# H1FR50.net
KiCad netlist of a schematic drawn in EAGLE
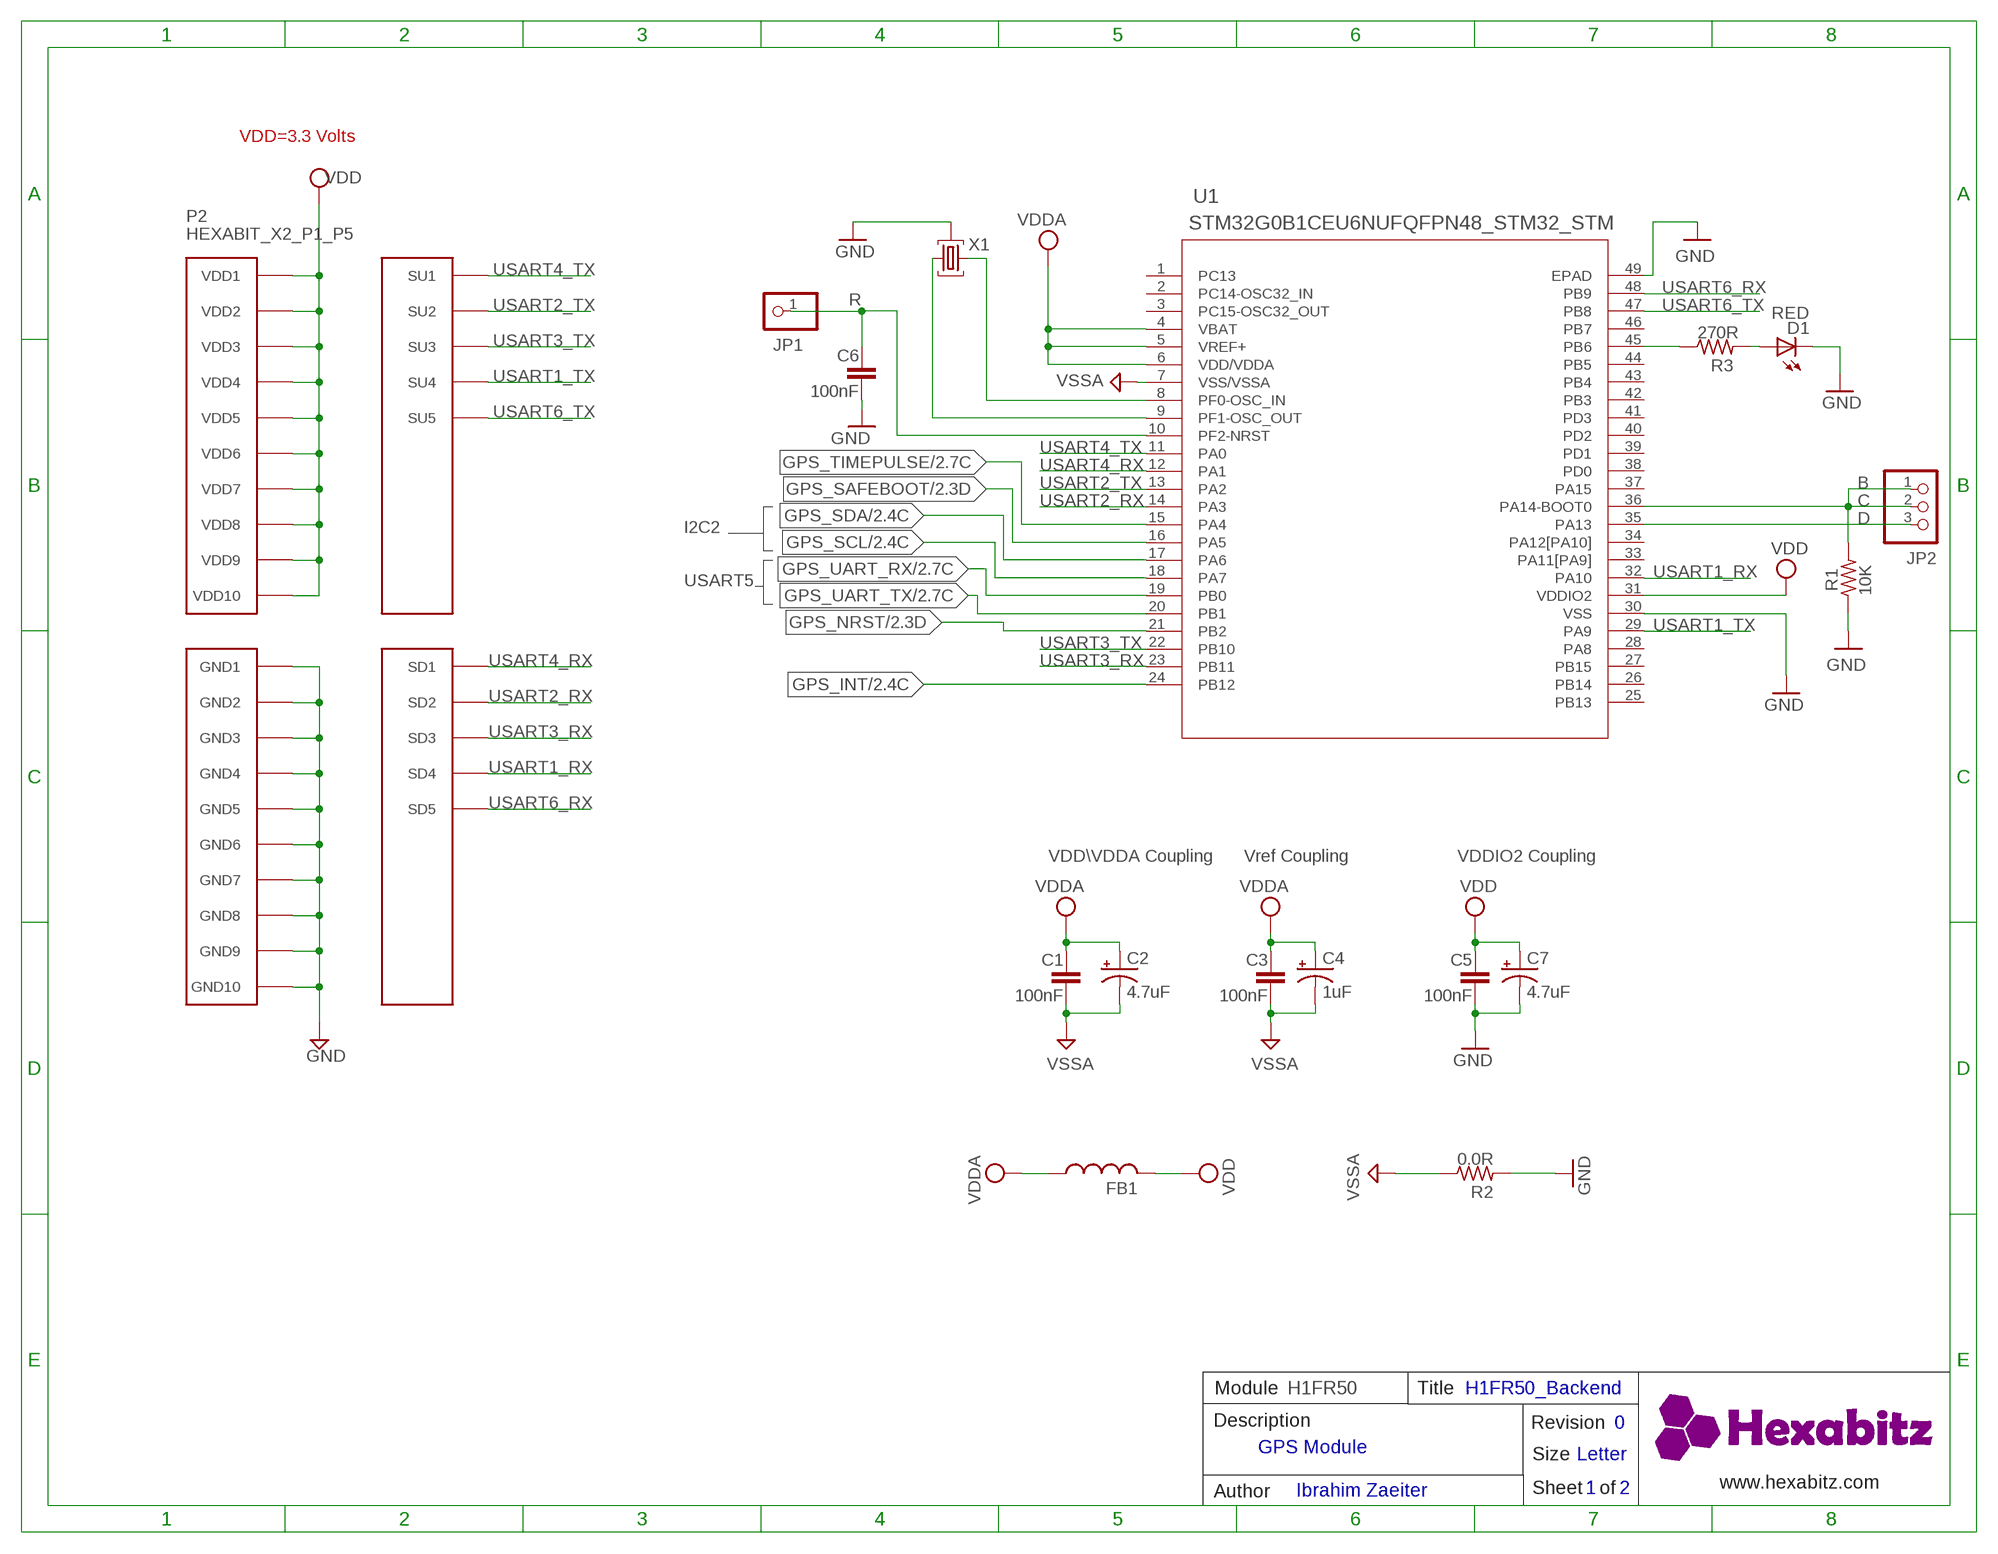
[diagram p0: schematic, sheet 1]
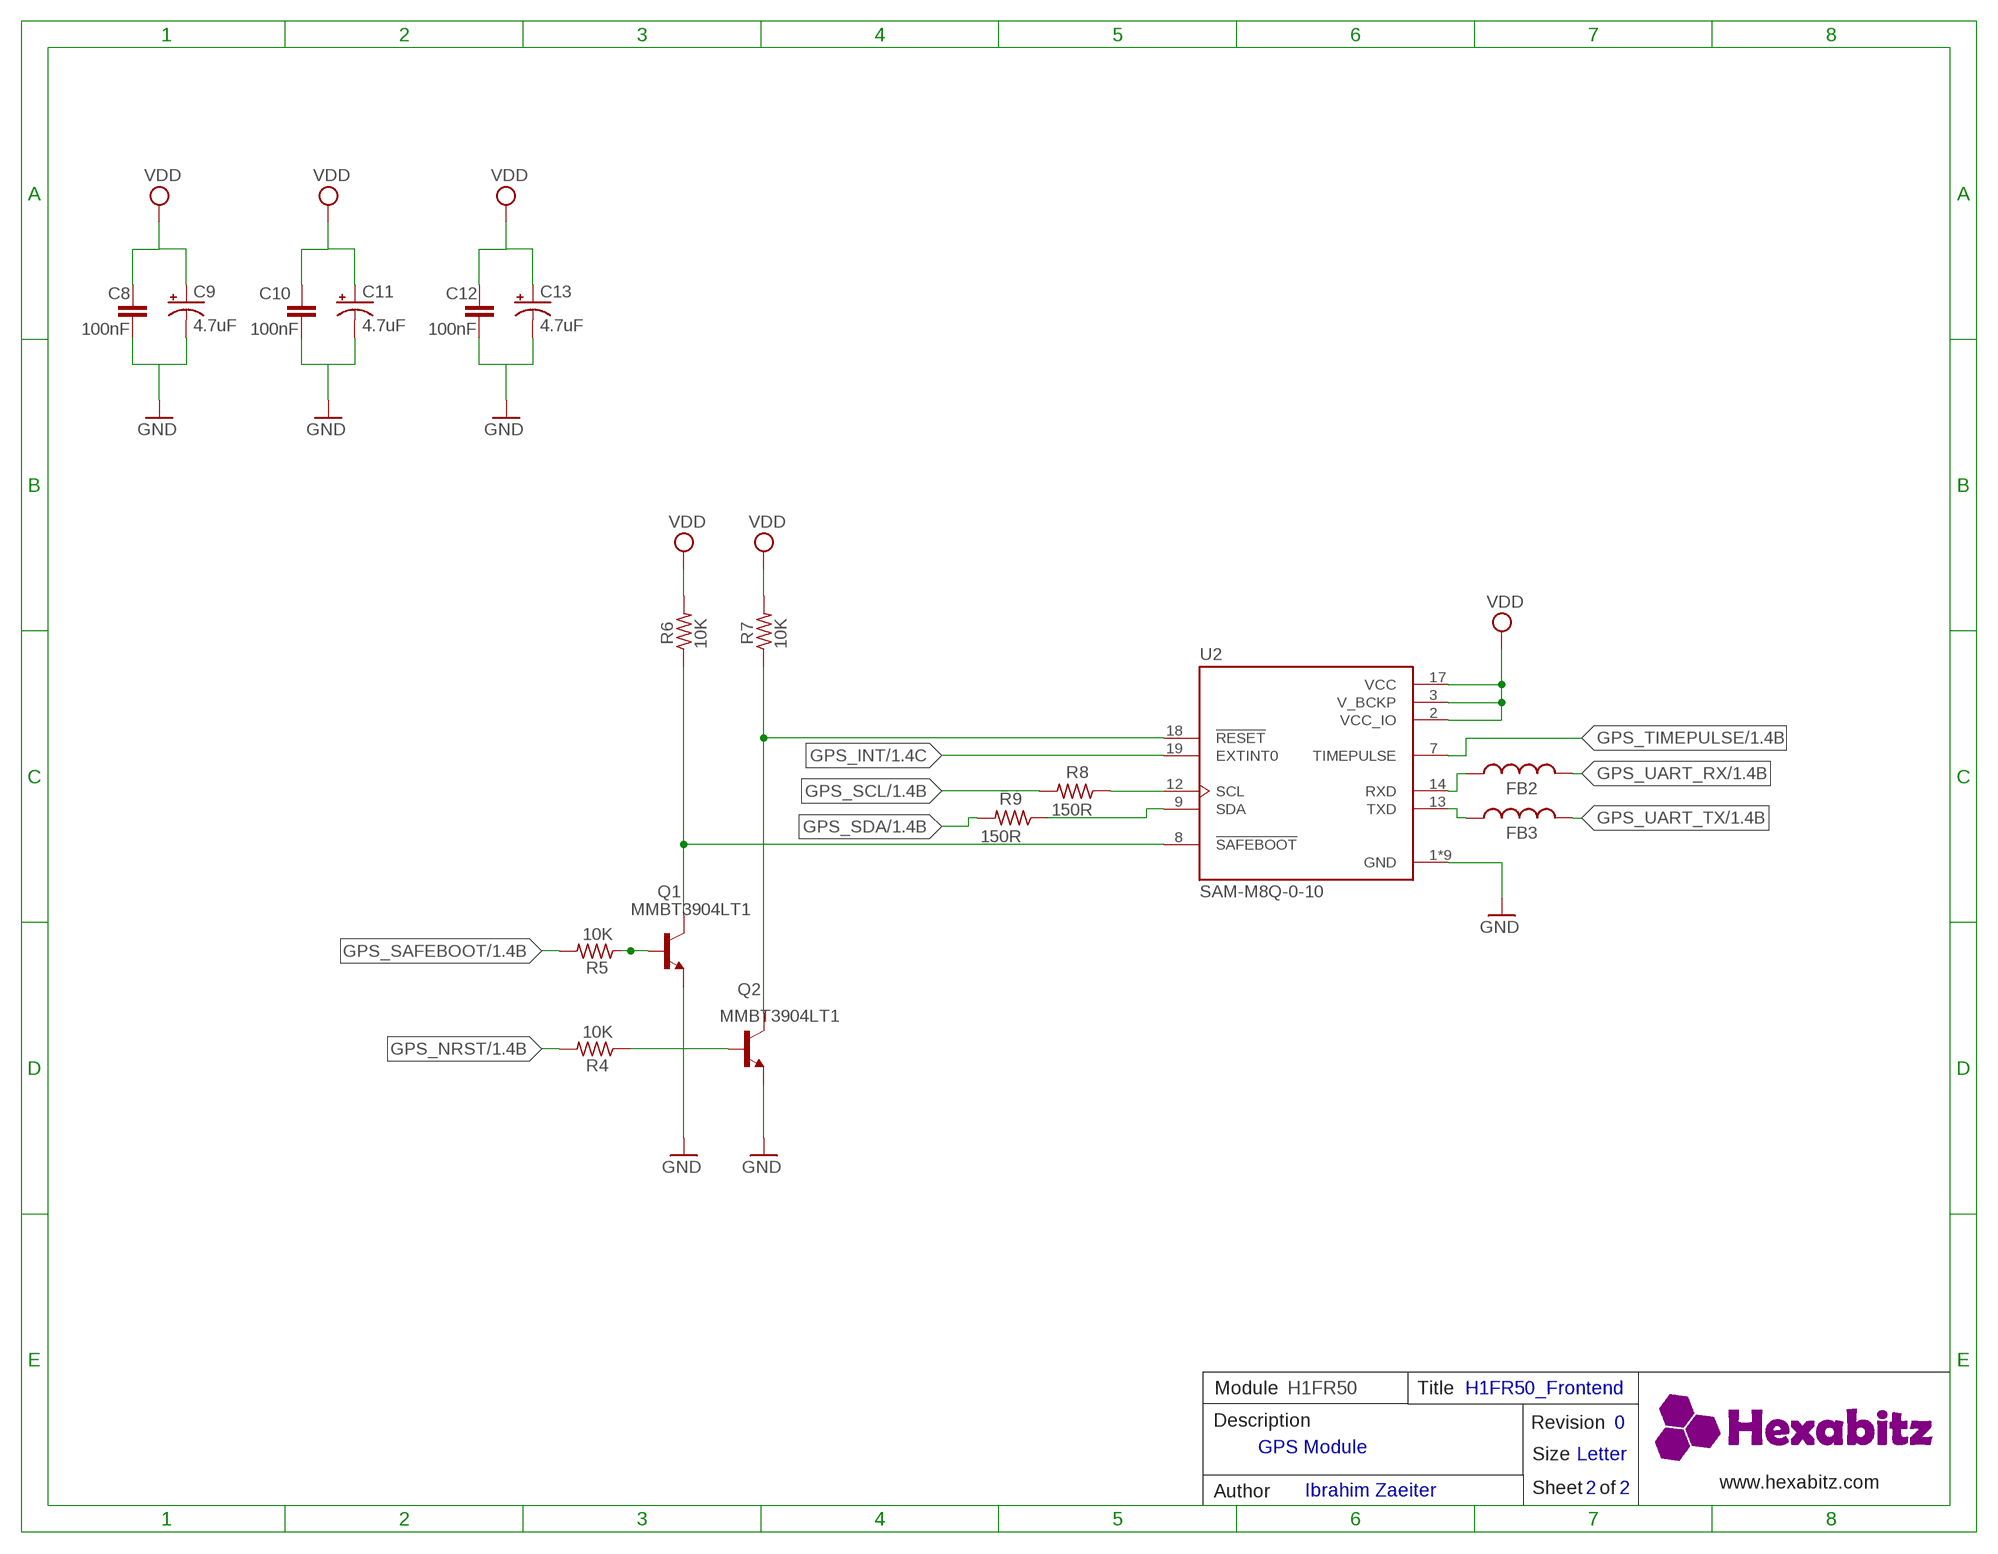
[diagram p1: schematic, sheet 2]

(export (version "E")
  (design (tool "Eeschema 10.0.6"))
  (components
    (comp (ref "C8")
      (value "100nF")
      (footprint "eagle-import:C-0603")
      (libsource (lib "eagle-import") (part "C-0603"))
    )
    (comp (ref "C9")
      (value "4.7uF")
      (footprint "eagle-import:C-0805-POL")
      (libsource (lib "eagle-import") (part "C-0805-POL"))
    )
    (comp (ref "C10")
      (value "100nF")
      (footprint "eagle-import:C-0603")
      (libsource (lib "eagle-import") (part "C-0603"))
    )
    (comp (ref "C11")
      (value "4.7uF")
      (footprint "eagle-import:C-0805-POL")
      (libsource (lib "eagle-import") (part "C-0805-POL"))
    )
    (comp (ref "C12")
      (value "100nF")
      (footprint "eagle-import:C-0603")
      (libsource (lib "eagle-import") (part "C-0603"))
    )
    (comp (ref "C13")
      (value "4.7uF")
      (footprint "eagle-import:C-0805-POL")
      (libsource (lib "eagle-import") (part "C-0805-POL"))
    )
    (comp (ref "FB2")
      (value "BLM18KG601SN1D")
      (footprint "eagle-import:FB-0603")
      (libsource (lib "eagle-import") (part "FB-0603"))
    )
    (comp (ref "FB3")
      (value "BLM18KG601SN1D")
      (footprint "eagle-import:FB-0603")
      (libsource (lib "eagle-import") (part "FB-0603"))
    )
    (comp (ref "Q1")
      (value "MMBT3904LT1")
      (footprint "eagle-import:MMBT3904LT1")
      (libsource (lib "eagle-import") (part "MMBT3904LT1"))
    )
    (comp (ref "Q2")
      (value "MMBT3904LT1")
      (footprint "eagle-import:MMBT3904LT1")
      (libsource (lib "eagle-import") (part "MMBT3904LT1"))
    )
    (comp (ref "R4")
      (value "10K")
      (footprint "eagle-import:R-0603")
      (libsource (lib "eagle-import") (part "R-0603"))
    )
    (comp (ref "R5")
      (value "10K")
      (footprint "eagle-import:R-0603")
      (libsource (lib "eagle-import") (part "R-0603"))
    )
    (comp (ref "R6")
      (value "10K")
      (footprint "eagle-import:R-0603")
      (libsource (lib "eagle-import") (part "R-0603"))
    )
    (comp (ref "R7")
      (value "10K")
      (footprint "eagle-import:R-0603")
      (libsource (lib "eagle-import") (part "R-0603"))
    )
    (comp (ref "R8")
      (value "150R")
      (footprint "eagle-import:R-0603")
      (fields (field (name "MPN") "CRCW0603150RFKEA"))
      (libsource (lib "eagle-import") (part "R-0603"))
    )
    (comp (ref "R9")
      (value "150R")
      (footprint "eagle-import:R-0603")
      (fields (field (name "MPN") "CRCW0603150RFKEA"))
      (libsource (lib "eagle-import") (part "R-0603"))
    )
    (comp (ref "U2")
      (value "SAM-M8Q-0-10")
      (footprint "eagle-import:MODULE_SAM-M8Q-0-10")
      (fields (field (name "MF") "U-Blox"))
      (libsource (lib "eagle-import") (part "SAM-M8Q-0-10"))
    )
    (comp (ref "C1")
      (value "100nF")
      (footprint "eagle-import:C-0603")
      (libsource (lib "eagle-import") (part "C-0603"))
    )
    (comp (ref "C2")
      (value "4.7uF")
      (footprint "eagle-import:C-0805-POL")
      (libsource (lib "eagle-import") (part "C-0805-POL"))
    )
    (comp (ref "C3")
      (value "100nF")
      (footprint "eagle-import:C-0603")
      (libsource (lib "eagle-import") (part "C-0603"))
    )
    (comp (ref "C4")
      (value "1uF")
      (footprint "eagle-import:C-0805-POL")
      (libsource (lib "eagle-import") (part "C-0805-POL"))
    )
    (comp (ref "C5")
      (value "100nF")
      (footprint "eagle-import:C-0603")
      (libsource (lib "eagle-import") (part "C-0603"))
    )
    (comp (ref "C6")
      (value "100nF")
      (footprint "eagle-import:C-0603")
      (libsource (lib "eagle-import") (part "C-0603"))
    )
    (comp (ref "C7")
      (value "4.7uF")
      (footprint "eagle-import:C-0805-POL")
      (libsource (lib "eagle-import") (part "C-0805-POL"))
    )
    (comp (ref "D1")
      (value "RED")
      (footprint "eagle-import:VLMS1300-GS08")
      (fields (field (name "MPN") "VLMS1300-GS08"))
      (libsource (lib "eagle-import") (part "VLMS1300-GS08"))
    )
    (comp (ref "FB1")
      (value "FB-0603")
      (footprint "eagle-import:FB-0603")
      (libsource (lib "eagle-import") (part "FB-0603"))
    )
    (comp (ref "JP1")
      (value "R")
      (footprint "eagle-import:1X01")
      (fields (field (name "MPN") "87227-1"))
      (libsource (lib "eagle-import") (part "PINHD-1X1"))
    )
    (comp (ref "JP2")
      (value "PINHD-1X3")
      (footprint "eagle-import:1X03")
      (libsource (lib "eagle-import") (part "PINHD-1X3"))
    )
    (comp (ref "P2")
      (value "HEXABIT_X2_P1_P5")
      (footprint "eagle-import:HEXABIT_17.32_X2_P1_P5")
      (libsource (lib "eagle-import") (part "HEXABIT_X2_P1_P5"))
    )
    (comp (ref "R1")
      (value "10K")
      (footprint "eagle-import:R-0603")
      (libsource (lib "eagle-import") (part "R-0603"))
    )
    (comp (ref "R2")
      (value "0.0R")
      (footprint "eagle-import:R-0603")
      (libsource (lib "eagle-import") (part "R-0603"))
    )
    (comp (ref "R3")
      (value "270R")
      (footprint "eagle-import:R-0603")
      (libsource (lib "eagle-import") (part "R-0603"))
    )
    (comp (ref "U1")
      (value "STM32G0B1CEU6NUFQFPN48_STM32_STM")
      (footprint "eagle-import:UFQFPN48_STM32_STM")
      (fields
        (field (name "MPN") "STM32G0B1CEU6N")
        (field (name "COPYRIGHT") "Copyright (C) 2022 Ultra Librarian. All rights reserved.")
      )
      (libsource (lib "eagle-import") (part "STM32G0B1CEU6NUFQFPN48_STM32_STM"))
    )
    (comp (ref "X1")
      (value "XTALL_CSTCE8M00G52")
      (footprint "eagle-import:XTALL_CSTCE8M00G52")
      (fields (field (name "MPN") "CSTCE8M00G52Z-R0"))
      (libsource (lib "eagle-import") (part "XTALL_CSTCE8M00G52"))
    )
  )
  (nets
    (net (code "1") (name "C") (class "Default")
      (node (ref "JP2") (pin "1") (pinfunction "1_1") (pintype "passive"))
      (node (ref "JP2") (pin "2") (pinfunction "2_2") (pintype "passive"))
      (node (ref "R1") (pin "2") (pinfunction "2_2") (pintype "passive"))
      (node (ref "U1") (pin "36") (pinfunction "PA14-BOOT0_36") (pintype "bidirectional"))
    )
    (net (code "2") (name "D") (class "Default")
      (node (ref "JP2") (pin "3") (pinfunction "3_3") (pintype "passive"))
      (node (ref "U1") (pin "35") (pinfunction "PA13_35") (pintype "bidirectional"))
    )
    (net (code "3") (name "GND") (class "Default")
      (node (ref "C10") (pin "2") (pinfunction "2_2") (pintype "passive"))
      (node (ref "C11") (pin "2") (pinfunction "-_2") (pintype "passive"))
      (node (ref "C12") (pin "2") (pinfunction "2_2") (pintype "passive"))
      (node (ref "C13") (pin "2") (pinfunction "-_2") (pintype "passive"))
      (node (ref "C5") (pin "2") (pinfunction "2_2") (pintype "passive"))
      (node (ref "C6") (pin "2") (pinfunction "2_2") (pintype "passive"))
      (node (ref "C7") (pin "2") (pinfunction "-_2") (pintype "passive"))
      (node (ref "C8") (pin "2") (pinfunction "2_2") (pintype "passive"))
      (node (ref "C9") (pin "2") (pinfunction "-_2") (pintype "passive"))
      (node (ref "D1") (pin "C") (pinfunction "C_C") (pintype "passive"))
      (node (ref "P2") (pin "PAD_PD11") (pinfunction "GND1_PAD_PD11") (pintype "power_in"))
      (node (ref "P2") (pin "PAD_PD12") (pinfunction "GND2_PAD_PD12") (pintype "power_in"))
      (node (ref "P2") (pin "PAD_PD13") (pinfunction "GND3_PAD_PD13") (pintype "power_in"))
      (node (ref "P2") (pin "PAD_PD14") (pinfunction "GND4_PAD_PD14") (pintype "power_in"))
      (node (ref "P2") (pin "PAD_PD15") (pinfunction "GND5_PAD_PD15") (pintype "power_in"))
      (node (ref "P2") (pin "PAD_PD16") (pinfunction "GND6_PAD_PD16") (pintype "power_in"))
      (node (ref "P2") (pin "PAD_PD17") (pinfunction "GND7_PAD_PD17") (pintype "power_in"))
      (node (ref "P2") (pin "PAD_PD18") (pinfunction "GND8_PAD_PD18") (pintype "power_in"))
      (node (ref "P2") (pin "PAD_PD19") (pinfunction "GND9_PAD_PD19") (pintype "power_in"))
      (node (ref "P2") (pin "PAD_PD20") (pinfunction "GND10_PAD_PD20") (pintype "power_in"))
      (node (ref "Q1") (pin "2") (pinfunction "E_2") (pintype "passive"))
      (node (ref "Q2") (pin "2") (pinfunction "E_2") (pintype "passive"))
      (node (ref "R1") (pin "1") (pinfunction "1_1") (pintype "passive"))
      (node (ref "R2") (pin "2") (pinfunction "2_2") (pintype "passive"))
      (node (ref "U1") (pin "30") (pinfunction "VSS_30") (pintype "passive"))
      (node (ref "U1") (pin "49") (pinfunction "EPAD_49") (pintype "passive"))
      (node (ref "U2") (pin "1") (pinfunction "GND_1") (pintype "power_in"))
      (node (ref "U2") (pin "10") (pinfunction "GND_10") (pintype "power_in"))
      (node (ref "U2") (pin "11") (pinfunction "GND_11") (pintype "power_in"))
      (node (ref "U2") (pin "15") (pinfunction "GND_15") (pintype "power_in"))
      (node (ref "U2") (pin "16") (pinfunction "GND_16") (pintype "power_in"))
      (node (ref "U2") (pin "20") (pinfunction "GND_20") (pintype "power_in"))
      (node (ref "U2") (pin "4") (pinfunction "GND_4") (pintype "power_in"))
      (node (ref "U2") (pin "5") (pinfunction "GND_5") (pintype "power_in"))
      (node (ref "U2") (pin "6") (pinfunction "GND_6") (pintype "power_in"))
      (node (ref "X1") (pin "P$2") (pinfunction "2_P$2") (pintype "passive"))
    )
    (net (code "4") (name "GPS_INT") (class "Default")
      (node (ref "U1") (pin "24") (pinfunction "PB12_24") (pintype "bidirectional"))
      (node (ref "U2") (pin "19") (pinfunction "EXTINT0_19") (pintype "input"))
    )
    (net (code "5") (name "GPS_NRST") (class "Default")
      (node (ref "R4") (pin "2") (pinfunction "2_2") (pintype "passive"))
      (node (ref "U1") (pin "21") (pinfunction "PB2_21") (pintype "bidirectional"))
    )
    (net (code "6") (name "GPS_SAFEBOOT") (class "Default")
      (node (ref "R5") (pin "2") (pinfunction "2_2") (pintype "passive"))
      (node (ref "U1") (pin "16") (pinfunction "PA5_16") (pintype "bidirectional"))
    )
    (net (code "7") (name "GPS_SCL") (class "Default")
      (node (ref "R8") (pin "2") (pinfunction "2_2") (pintype "passive"))
      (node (ref "U1") (pin "18") (pinfunction "PA7_18") (pintype "bidirectional"))
    )
    (net (code "8") (name "GPS_SDA") (class "Default")
      (node (ref "R9") (pin "2") (pinfunction "2_2") (pintype "passive"))
      (node (ref "U1") (pin "17") (pinfunction "PA6_17") (pintype "bidirectional"))
    )
    (net (code "9") (name "GPS_TIMEPULSE") (class "Default")
      (node (ref "U1") (pin "15") (pinfunction "PA4_15") (pintype "bidirectional"))
      (node (ref "U2") (pin "7") (pinfunction "TIMEPULSE_7") (pintype "output"))
    )
    (net (code "10") (name "GPS_UART_RX") (class "Default")
      (node (ref "FB2") (pin "2") (pinfunction "2_2") (pintype "passive"))
      (node (ref "U1") (pin "19") (pinfunction "PB0_19") (pintype "bidirectional"))
    )
    (net (code "11") (name "GPS_UART_TX") (class "Default")
      (node (ref "FB3") (pin "2") (pinfunction "2_2") (pintype "passive"))
      (node (ref "U1") (pin "20") (pinfunction "PB1_20") (pintype "bidirectional"))
    )
    (net (code "12") (name "Net-(D1-PadA)") (class "Default")
      (node (ref "D1") (pin "A") (pinfunction "A_A") (pintype "passive"))
      (node (ref "R3") (pin "2") (pinfunction "2_2") (pintype "passive"))
    )
    (net (code "13") (name "Net-(Q1-B)") (class "Default")
      (node (ref "Q1") (pin "1") (pinfunction "B_1") (pintype "passive"))
      (node (ref "R5") (pin "1") (pinfunction "1_1") (pintype "passive"))
    )
    (net (code "14") (name "Net-(Q1-C)") (class "Default")
      (node (ref "Q1") (pin "3") (pinfunction "C_3") (pintype "passive"))
      (node (ref "R6") (pin "1") (pinfunction "1_1") (pintype "passive"))
      (node (ref "U2") (pin "8") (pinfunction "~{SAFEBOOT}_8") (pintype "input"))
    )
    (net (code "15") (name "Net-(Q2-B)") (class "Default")
      (node (ref "Q2") (pin "1") (pinfunction "B_1") (pintype "passive"))
      (node (ref "R4") (pin "1") (pinfunction "1_1") (pintype "passive"))
    )
    (net (code "16") (name "Net-(Q2-C)") (class "Default")
      (node (ref "Q2") (pin "3") (pinfunction "C_3") (pintype "passive"))
      (node (ref "R7") (pin "1") (pinfunction "1_1") (pintype "passive"))
      (node (ref "U2") (pin "18") (pinfunction "~{RESET}_18") (pintype "input"))
    )
    (net (code "17") (name "Net-(U1-PB6)") (class "Default")
      (node (ref "R3") (pin "1") (pinfunction "1_1") (pintype "passive"))
      (node (ref "U1") (pin "45") (pinfunction "PB6_45") (pintype "bidirectional"))
    )
    (net (code "18") (name "Net-(U1-PF0-OSC_IN)") (class "Default")
      (node (ref "U1") (pin "8") (pinfunction "PF0-OSC_IN_8") (pintype "bidirectional"))
      (node (ref "X1") (pin "P$1") (pinfunction "1_P$1") (pintype "passive"))
    )
    (net (code "19") (name "Net-(U1-PF1-OSC_OUT)") (class "Default")
      (node (ref "U1") (pin "9") (pinfunction "PF1-OSC_OUT_9") (pintype "bidirectional"))
      (node (ref "X1") (pin "P$3") (pinfunction "3_P$3") (pintype "passive"))
    )
    (net (code "20") (name "Net-(U1-PF2-NRST)") (class "Default")
      (node (ref "C6") (pin "1") (pinfunction "1_1") (pintype "passive"))
      (node (ref "JP1") (pin "1") (pinfunction "1_1") (pintype "passive"))
      (node (ref "U1") (pin "10") (pinfunction "PF2-NRST_10") (pintype "bidirectional"))
    )
    (net (code "21") (name "Net-(U2-RXD)") (class "Default")
      (node (ref "FB2") (pin "1") (pinfunction "1_1") (pintype "passive"))
      (node (ref "U2") (pin "14") (pinfunction "RXD_14") (pintype "input"))
    )
    (net (code "22") (name "Net-(U2-SCL)") (class "Default")
      (node (ref "R8") (pin "1") (pinfunction "1_1") (pintype "passive"))
      (node (ref "U2") (pin "12") (pinfunction "SCL_12") (pintype "input"))
    )
    (net (code "23") (name "Net-(U2-SDA)") (class "Default")
      (node (ref "R9") (pin "1") (pinfunction "1_1") (pintype "passive"))
      (node (ref "U2") (pin "9") (pinfunction "SDA_9") (pintype "bidirectional"))
    )
    (net (code "24") (name "Net-(U2-TXD)") (class "Default")
      (node (ref "FB3") (pin "1") (pinfunction "1_1") (pintype "passive"))
      (node (ref "U2") (pin "13") (pinfunction "TXD_13") (pintype "output"))
    )
    (net (code "25") (name "USART1_RX") (class "Default")
      (node (ref "P2") (pin "PAD_PD4") (pinfunction "SD4_PAD_PD4") (pintype "bidirectional"))
      (node (ref "U1") (pin "32") (pinfunction "PA10_32") (pintype "bidirectional"))
    )
    (net (code "26") (name "USART1_TX") (class "Default")
      (node (ref "P2") (pin "PAD_PU4") (pinfunction "SU4_PAD_PU4") (pintype "bidirectional"))
      (node (ref "U1") (pin "29") (pinfunction "PA9_29") (pintype "bidirectional"))
    )
    (net (code "27") (name "USART2_RX") (class "Default")
      (node (ref "P2") (pin "PAD_PD2") (pinfunction "SD2_PAD_PD2") (pintype "bidirectional"))
      (node (ref "U1") (pin "14") (pinfunction "PA3_14") (pintype "bidirectional"))
    )
    (net (code "28") (name "USART2_TX") (class "Default")
      (node (ref "P2") (pin "PAD_PU2") (pinfunction "SU2_PAD_PU2") (pintype "bidirectional"))
      (node (ref "U1") (pin "13") (pinfunction "PA2_13") (pintype "bidirectional"))
    )
    (net (code "29") (name "USART3_RX") (class "Default")
      (node (ref "P2") (pin "PAD_PD3") (pinfunction "SD3_PAD_PD3") (pintype "bidirectional"))
      (node (ref "U1") (pin "23") (pinfunction "PB11_23") (pintype "bidirectional"))
    )
    (net (code "30") (name "USART3_TX") (class "Default")
      (node (ref "P2") (pin "PAD_PU3") (pinfunction "SU3_PAD_PU3") (pintype "bidirectional"))
      (node (ref "U1") (pin "22") (pinfunction "PB10_22") (pintype "bidirectional"))
    )
    (net (code "31") (name "USART4_RX") (class "Default")
      (node (ref "P2") (pin "PAD_PD1") (pinfunction "SD1_PAD_PD1") (pintype "bidirectional"))
      (node (ref "U1") (pin "12") (pinfunction "PA1_12") (pintype "bidirectional"))
    )
    (net (code "32") (name "USART4_TX") (class "Default")
      (node (ref "P2") (pin "PAD_PU1") (pinfunction "SU1_PAD_PU1") (pintype "bidirectional"))
      (node (ref "U1") (pin "11") (pinfunction "PA0_11") (pintype "bidirectional"))
    )
    (net (code "33") (name "USART6_RX") (class "Default")
      (node (ref "P2") (pin "PAD_PD5") (pinfunction "SD5_PAD_PD5") (pintype "bidirectional"))
      (node (ref "U1") (pin "48") (pinfunction "PB9_48") (pintype "bidirectional"))
    )
    (net (code "34") (name "USART6_TX") (class "Default")
      (node (ref "P2") (pin "PAD_PU5") (pinfunction "SU5_PAD_PU5") (pintype "bidirectional"))
      (node (ref "U1") (pin "47") (pinfunction "PB8_47") (pintype "bidirectional"))
    )
    (net (code "35") (name "VDD") (class "Default")
      (node (ref "C10") (pin "1") (pinfunction "1_1") (pintype "passive"))
      (node (ref "C11") (pin "1") (pinfunction "+_1") (pintype "passive"))
      (node (ref "C12") (pin "1") (pinfunction "1_1") (pintype "passive"))
      (node (ref "C13") (pin "1") (pinfunction "+_1") (pintype "passive"))
      (node (ref "C5") (pin "1") (pinfunction "1_1") (pintype "passive"))
      (node (ref "C7") (pin "1") (pinfunction "+_1") (pintype "passive"))
      (node (ref "C8") (pin "1") (pinfunction "1_1") (pintype "passive"))
      (node (ref "C9") (pin "1") (pinfunction "+_1") (pintype "passive"))
      (node (ref "FB1") (pin "2") (pinfunction "2_2") (pintype "passive"))
      (node (ref "P2") (pin "PAD_PU11") (pinfunction "VDD1_PAD_PU11") (pintype "power_in"))
      (node (ref "P2") (pin "PAD_PU12") (pinfunction "VDD2_PAD_PU12") (pintype "power_in"))
      (node (ref "P2") (pin "PAD_PU13") (pinfunction "VDD3_PAD_PU13") (pintype "power_in"))
      (node (ref "P2") (pin "PAD_PU14") (pinfunction "VDD4_PAD_PU14") (pintype "power_in"))
      (node (ref "P2") (pin "PAD_PU15") (pinfunction "VDD5_PAD_PU15") (pintype "power_in"))
      (node (ref "P2") (pin "PAD_PU16") (pinfunction "VDD6_PAD_PU16") (pintype "power_in"))
      (node (ref "P2") (pin "PAD_PU17") (pinfunction "VDD7_PAD_PU17") (pintype "power_in"))
      (node (ref "P2") (pin "PAD_PU18") (pinfunction "VDD8_PAD_PU18") (pintype "power_in"))
      (node (ref "P2") (pin "PAD_PU19") (pinfunction "VDD9_PAD_PU19") (pintype "power_in"))
      (node (ref "P2") (pin "PAD_PU20") (pinfunction "VDD10_PAD_PU20") (pintype "power_in"))
      (node (ref "R6") (pin "2") (pinfunction "2_2") (pintype "passive"))
      (node (ref "R7") (pin "2") (pinfunction "2_2") (pintype "passive"))
      (node (ref "U1") (pin "31") (pinfunction "VDDIO2_31") (pintype "power_in"))
      (node (ref "U2") (pin "17") (pinfunction "VCC_17") (pintype "power_in"))
      (node (ref "U2") (pin "2") (pinfunction "VCC_IO_2") (pintype "power_in"))
      (node (ref "U2") (pin "3") (pinfunction "V_BCKP_3") (pintype "power_in"))
    )
    (net (code "36") (name "VDDA") (class "Default")
      (node (ref "C1") (pin "1") (pinfunction "1_1") (pintype "passive"))
      (node (ref "C2") (pin "1") (pinfunction "+_1") (pintype "passive"))
      (node (ref "C3") (pin "1") (pinfunction "1_1") (pintype "passive"))
      (node (ref "C4") (pin "1") (pinfunction "+_1") (pintype "passive"))
      (node (ref "FB1") (pin "1") (pinfunction "1_1") (pintype "passive"))
      (node (ref "U1") (pin "4") (pinfunction "VBAT_4") (pintype "power_in"))
      (node (ref "U1") (pin "5") (pinfunction "VREF+_5") (pintype "power_in"))
      (node (ref "U1") (pin "6") (pinfunction "VDD/VDDA_6") (pintype "power_in"))
    )
    (net (code "37") (name "VSSA") (class "Default")
      (node (ref "C1") (pin "2") (pinfunction "2_2") (pintype "passive"))
      (node (ref "C2") (pin "2") (pinfunction "-_2") (pintype "passive"))
      (node (ref "C3") (pin "2") (pinfunction "2_2") (pintype "passive"))
      (node (ref "C4") (pin "2") (pinfunction "-_2") (pintype "passive"))
      (node (ref "R2") (pin "1") (pinfunction "1_1") (pintype "passive"))
      (node (ref "U1") (pin "7") (pinfunction "VSS/VSSA_7") (pintype "passive"))
    )
    (net (code "38") (name "unconnected-(U1-PA8-Pad28)") (class "Default")
      (node (ref "U1") (pin "28") (pinfunction "PA8_28") (pintype "bidirectional"))
    )
    (net (code "39") (name "unconnected-(U1-PA11[PA9]-Pad33)") (class "Default")
      (node (ref "U1") (pin "33") (pinfunction "PA11[PA9]_33") (pintype "bidirectional"))
    )
    (net (code "40") (name "unconnected-(U1-PA12[PA10]-Pad34)") (class "Default")
      (node (ref "U1") (pin "34") (pinfunction "PA12[PA10]_34") (pintype "bidirectional"))
    )
    (net (code "41") (name "unconnected-(U1-PA15-Pad37)") (class "Default")
      (node (ref "U1") (pin "37") (pinfunction "PA15_37") (pintype "bidirectional"))
    )
    (net (code "42") (name "unconnected-(U1-PB3-Pad42)") (class "Default")
      (node (ref "U1") (pin "42") (pinfunction "PB3_42") (pintype "bidirectional"))
    )
    (net (code "43") (name "unconnected-(U1-PB4-Pad43)") (class "Default")
      (node (ref "U1") (pin "43") (pinfunction "PB4_43") (pintype "bidirectional"))
    )
    (net (code "44") (name "unconnected-(U1-PB5-Pad44)") (class "Default")
      (node (ref "U1") (pin "44") (pinfunction "PB5_44") (pintype "bidirectional"))
    )
    (net (code "45") (name "unconnected-(U1-PB7-Pad46)") (class "Default")
      (node (ref "U1") (pin "46") (pinfunction "PB7_46") (pintype "bidirectional"))
    )
    (net (code "46") (name "unconnected-(U1-PB13-Pad25)") (class "Default")
      (node (ref "U1") (pin "25") (pinfunction "PB13_25") (pintype "bidirectional"))
    )
    (net (code "47") (name "unconnected-(U1-PB14-Pad26)") (class "Default")
      (node (ref "U1") (pin "26") (pinfunction "PB14_26") (pintype "bidirectional"))
    )
    (net (code "48") (name "unconnected-(U1-PB15-Pad27)") (class "Default")
      (node (ref "U1") (pin "27") (pinfunction "PB15_27") (pintype "bidirectional"))
    )
    (net (code "49") (name "unconnected-(U1-PC13-Pad1)") (class "Default")
      (node (ref "U1") (pin "1") (pinfunction "PC13_1") (pintype "bidirectional"))
    )
    (net (code "50") (name "unconnected-(U1-PC14-OSC32_IN-Pad2)") (class "Default")
      (node (ref "U1") (pin "2") (pinfunction "PC14-OSC32_IN_2") (pintype "bidirectional"))
    )
    (net (code "51") (name "unconnected-(U1-PC15-OSC32_OUT-Pad3)") (class "Default")
      (node (ref "U1") (pin "3") (pinfunction "PC15-OSC32_OUT_3") (pintype "bidirectional"))
    )
    (net (code "52") (name "unconnected-(U1-PD0-Pad38)") (class "Default")
      (node (ref "U1") (pin "38") (pinfunction "PD0_38") (pintype "bidirectional"))
    )
    (net (code "53") (name "unconnected-(U1-PD1-Pad39)") (class "Default")
      (node (ref "U1") (pin "39") (pinfunction "PD1_39") (pintype "bidirectional"))
    )
    (net (code "54") (name "unconnected-(U1-PD2-Pad40)") (class "Default")
      (node (ref "U1") (pin "40") (pinfunction "PD2_40") (pintype "bidirectional"))
    )
    (net (code "55") (name "unconnected-(U1-PD3-Pad41)") (class "Default")
      (node (ref "U1") (pin "41") (pinfunction "PD3_41") (pintype "bidirectional"))
    )
  )
)
